# Driver.net
KiCad netlist of a schematic drawn in EAGLE
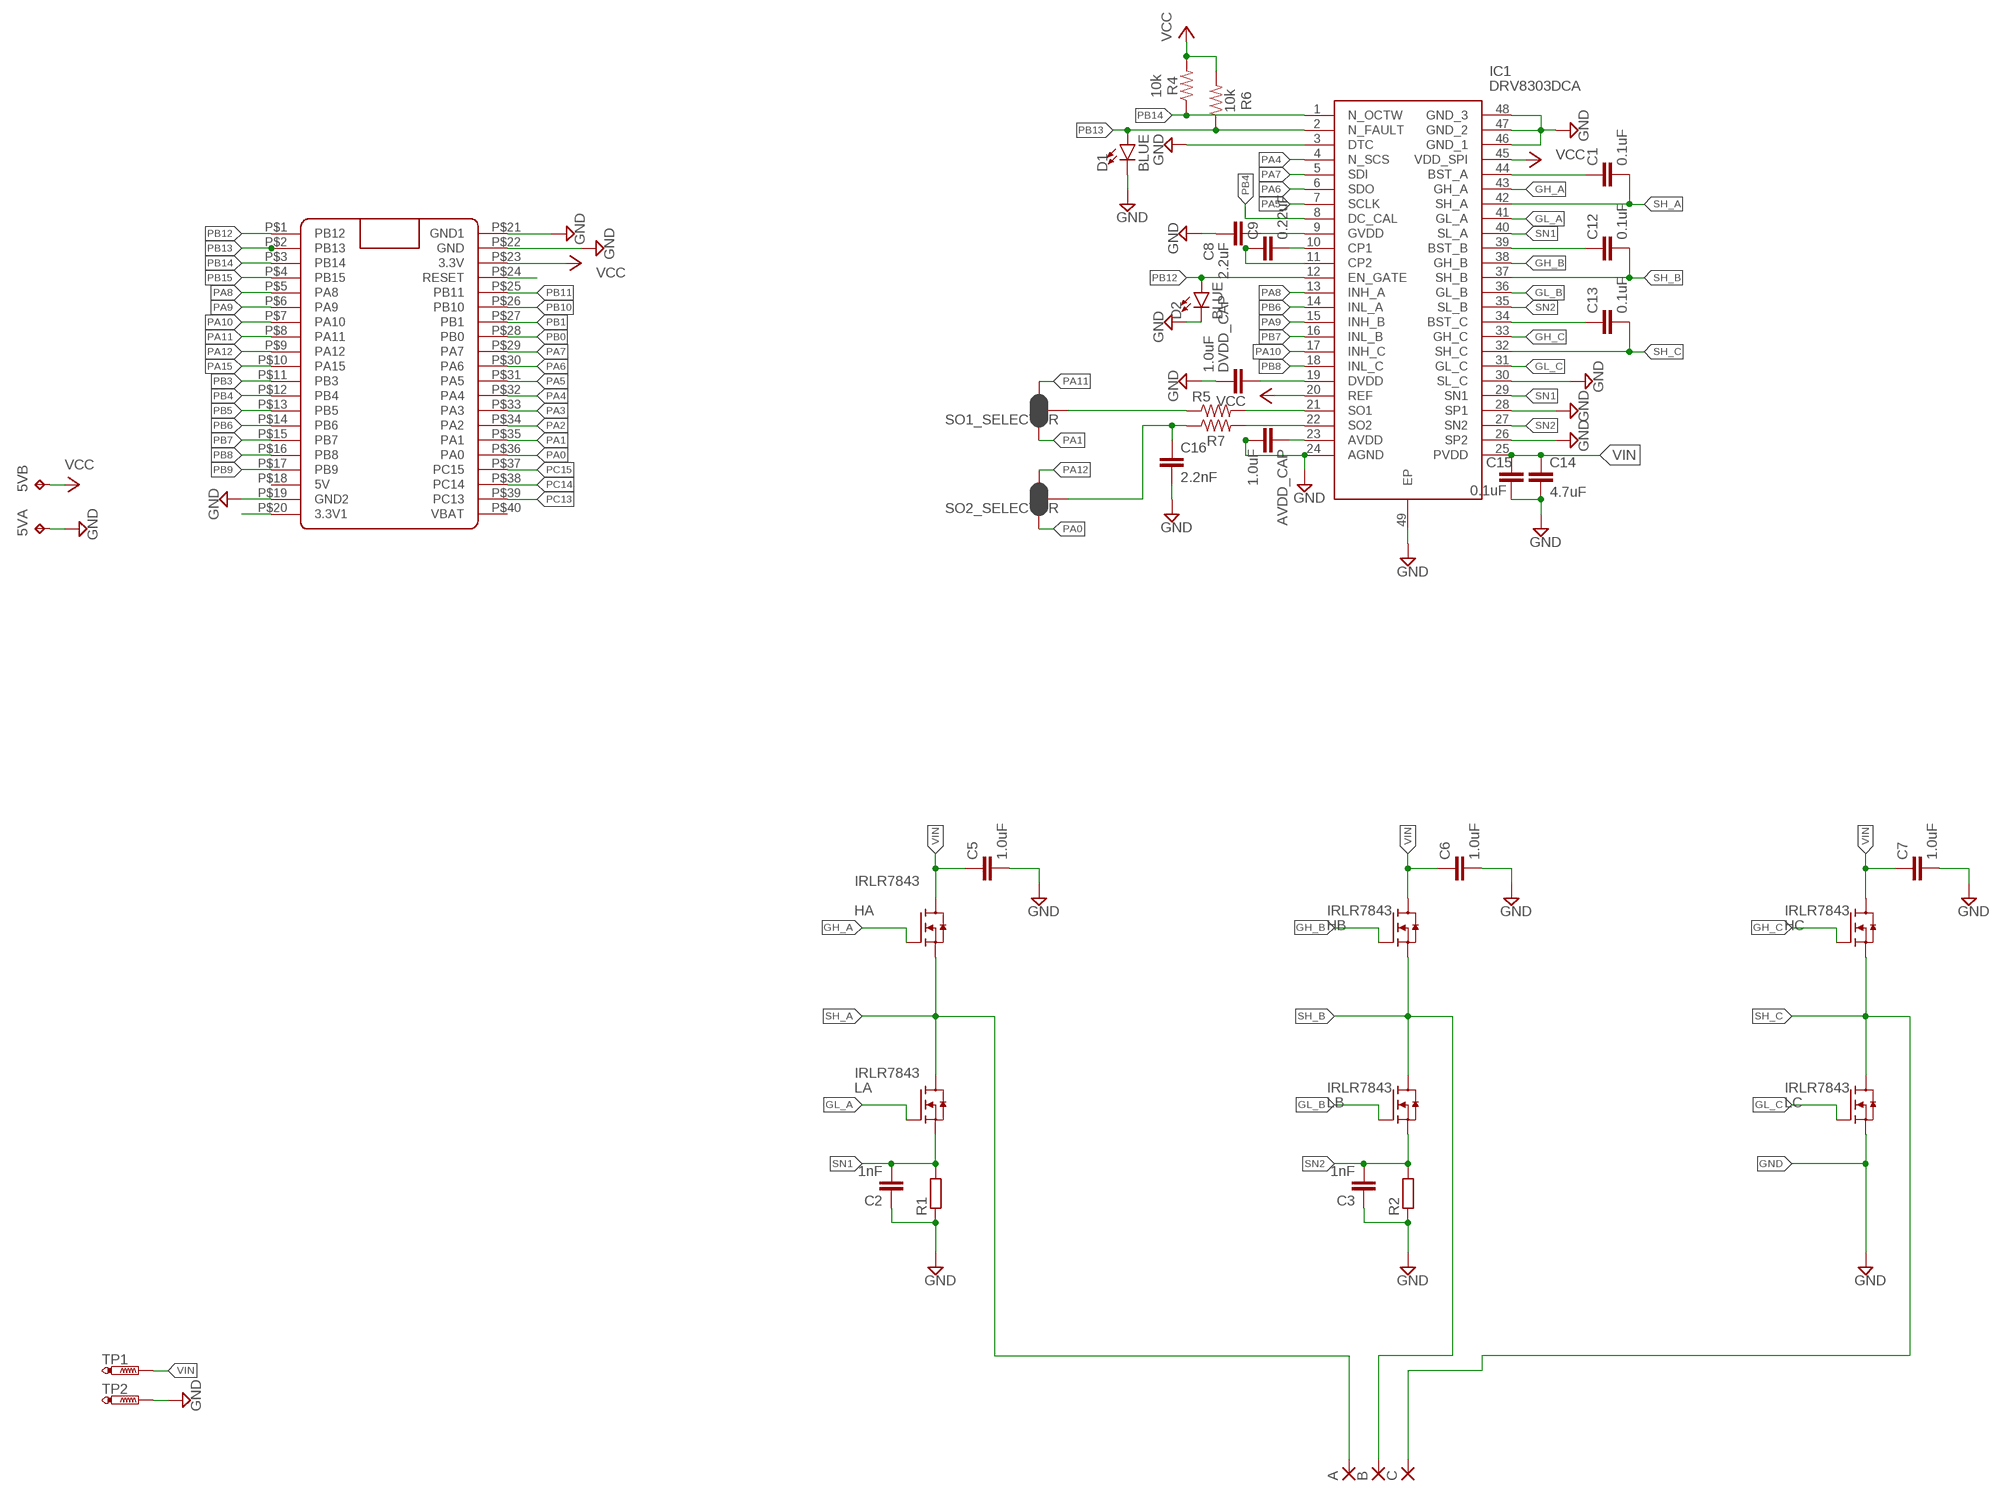
[diagram p0: schematic, sheet 1]

(export (version "E")
  (design (tool "Eeschema 10.0.6"))
  (components
    (comp (ref "5V")
      (value "TP2P2-38-17")
      (footprint "eagle-import:P2-38-17")
      (libsource (lib "eagle-import") (part "TP2P2-38-17"))
    )
    (comp (ref "A")
      (value "SMD5")
      (footprint "eagle-import:SMD2,54-5,08")
      (libsource (lib "eagle-import") (part "SMD5"))
    )
    (comp (ref "AVDD_CAP")
      (value "1.0uF")
      (footprint "eagle-import:0603")
      (libsource (lib "eagle-import") (part "1.0UF-0603-16V-10%"))
    )
    (comp (ref "B")
      (value "SMD5")
      (footprint "eagle-import:SMD2,54-5,08")
      (libsource (lib "eagle-import") (part "SMD5"))
    )
    (comp (ref "C")
      (value "SMD5")
      (footprint "eagle-import:SMD2,54-5,08")
      (libsource (lib "eagle-import") (part "SMD5"))
    )
    (comp (ref "C1")
      (value "0.1uF")
      (footprint "eagle-import:0603")
      (libsource (lib "eagle-import") (part "0.1UF-0603-25V-(+80/-20%)"))
    )
    (comp (ref "C2")
      (value "1nF")
      (footprint "eagle-import:0603")
      (libsource (lib "eagle-import") (part "1.0NF/1000PF-0603-50V-10%"))
    )
    (comp (ref "C3")
      (value "1nF")
      (footprint "eagle-import:0603")
      (libsource (lib "eagle-import") (part "1.0NF/1000PF-0603-50V-10%"))
    )
    (comp (ref "C5")
      (value "1.0uF")
      (footprint "eagle-import:0603")
      (libsource (lib "eagle-import") (part "1.0UF-0603-16V-10%-X7R"))
    )
    (comp (ref "C6")
      (value "1.0uF")
      (footprint "eagle-import:0603")
      (libsource (lib "eagle-import") (part "1.0UF-0603-16V-10%-X7R"))
    )
    (comp (ref "C7")
      (value "1.0uF")
      (footprint "eagle-import:0603")
      (libsource (lib "eagle-import") (part "1.0UF-0603-16V-10%-X7R"))
    )
    (comp (ref "C8")
      (value "2.2uF")
      (footprint "eagle-import:0603")
      (libsource (lib "eagle-import") (part "2.2UF-0603-10V-20%"))
    )
    (comp (ref "C9")
      (value "0.22uF")
      (footprint "eagle-import:0603")
      (libsource (lib "eagle-import") (part "0.22UF-0603-25V-10%"))
    )
    (comp (ref "C12")
      (value "0.1uF")
      (footprint "eagle-import:0603")
      (libsource (lib "eagle-import") (part "0.1UF-0603-25V-(+80/-20%)"))
    )
    (comp (ref "C13")
      (value "0.1uF")
      (footprint "eagle-import:0603")
      (libsource (lib "eagle-import") (part "0.1UF-0603-25V-(+80/-20%)"))
    )
    (comp (ref "C14")
      (value "4.7uF")
      (footprint "eagle-import:0603")
      (libsource (lib "eagle-import") (part "4.7UF-0603-35V-(20%)"))
    )
    (comp (ref "C15")
      (value "0.1uF")
      (footprint "eagle-import:0603")
      (libsource (lib "eagle-import") (part "0.1UF-0603-25V-(+80/-20%)"))
    )
    (comp (ref "C16")
      (value "2.2nF")
      (footprint "eagle-import:0603")
      (libsource (lib "eagle-import") (part "2.2NF/2200PF-0603-50V-10%"))
    )
    (comp (ref "D1")
      (value "BLUE")
      (footprint "eagle-import:LED-0603")
      (libsource (lib "eagle-import") (part "LED-BLUE0603"))
    )
    (comp (ref "D2")
      (value "BLUE")
      (footprint "eagle-import:LED-0603")
      (libsource (lib "eagle-import") (part "LED-BLUE0603"))
    )
    (comp (ref "DVDD_CAP")
      (value "1.0uF")
      (footprint "eagle-import:0603")
      (libsource (lib "eagle-import") (part "1.0UF-0603-16V-10%"))
    )
    (comp (ref "HA")
      (value "IRLR7843")
      (footprint "eagle-import:TO252")
      (libsource (lib "eagle-import") (part "IRLR7843"))
    )
    (comp (ref "HB")
      (value "IRLR7843")
      (footprint "eagle-import:TO252")
      (libsource (lib "eagle-import") (part "IRLR7843"))
    )
    (comp (ref "HC")
      (value "IRLR7843")
      (footprint "eagle-import:TO252")
      (libsource (lib "eagle-import") (part "IRLR7843"))
    )
    (comp (ref "IC1")
      (value "DRV8303DCA")
      (footprint "eagle-import:SOP50P810X120-49N")
      (fields (field (name "MOUSER_PART_NUMBER") "595-DRV8303DCA"))
      (libsource (lib "eagle-import") (part "DRV8303DCA"))
    )
    (comp (ref "LA")
      (value "IRLR7843")
      (footprint "eagle-import:TO252")
      (libsource (lib "eagle-import") (part "IRLR7843"))
    )
    (comp (ref "LB")
      (value "IRLR7843")
      (footprint "eagle-import:TO252")
      (libsource (lib "eagle-import") (part "IRLR7843"))
    )
    (comp (ref "LC")
      (value "IRLR7843")
      (footprint "eagle-import:TO252")
      (libsource (lib "eagle-import") (part "IRLR7843"))
    )
    (comp (ref "R1")
      (value "R-EU_R2512")
      (footprint "eagle-import:R2512")
      (libsource (lib "eagle-import") (part "R-EU_R2512"))
    )
    (comp (ref "R2")
      (value "R-EU_R2512")
      (footprint "eagle-import:R2512")
      (libsource (lib "eagle-import") (part "R-EU_R2512"))
    )
    (comp (ref "R4")
      (value "10k")
      (footprint "eagle-import:0603")
      (libsource (lib "eagle-import") (part "10KOHM-0603-1/10W-1%"))
    )
    (comp (ref "R5")
      (value "0")
      (footprint "eagle-import:0603")
      (libsource (lib "eagle-import") (part "0OHM-0603-1/10W"))
    )
    (comp (ref "R6")
      (value "10k")
      (footprint "eagle-import:0603")
      (libsource (lib "eagle-import") (part "10KOHM-0603-1/10W-1%"))
    )
    (comp (ref "R7")
      (value "0")
      (footprint "eagle-import:0603")
      (libsource (lib "eagle-import") (part "0OHM-0603-1/10W"))
    )
    (comp (ref "SO1_SELECTOR")
      (value "JUMPER-SMT_3_2-NC_PASTE_SILK")
      (footprint "eagle-import:SMT-JUMPER_3_2-NC_PASTE_SILK")
      (libsource (lib "eagle-import") (part "JUMPER-SMT_3_2-NC_PASTE_SILK"))
    )
    (comp (ref "SO2_SELECTOR")
      (value "JUMPER-SMT_3_2-NC_PASTE_SILK")
      (footprint "eagle-import:SMT-JUMPER_3_2-NC_PASTE_SILK")
      (libsource (lib "eagle-import") (part "JUMPER-SMT_3_2-NC_PASTE_SILK"))
    )
    (comp (ref "TP1")
      (value "PTR1PAD1-20Y")
      (footprint "eagle-import:P1-20Y")
      (libsource (lib "eagle-import") (part "PTR1PAD1-20Y"))
    )
    (comp (ref "TP2")
      (value "PTR1PAD1-20Y")
      (footprint "eagle-import:P1-20Y")
      (libsource (lib "eagle-import") (part "PTR1PAD1-20Y"))
    )
    (comp (ref "U$1")
      (value "BLUE_PILLADVANCED")
      (footprint "eagle-import:BLUE_PILL_ADV")
      (libsource (lib "eagle-import") (part "BLUE_PILLADVANCED"))
    )
  )
  (nets
    (net (code "1") (name "GH_A") (class "Default")
      (node (ref "HA") (pin "1") (pinfunction "G_1") (pintype "passive"))
      (node (ref "IC1") (pin "43") (pinfunction "GH_A_43") (pintype "output"))
    )
    (net (code "2") (name "GH_B") (class "Default")
      (node (ref "HB") (pin "1") (pinfunction "G_1") (pintype "passive"))
      (node (ref "IC1") (pin "38") (pinfunction "GH_B_38") (pintype "output"))
    )
    (net (code "3") (name "GH_C") (class "Default")
      (node (ref "HC") (pin "1") (pinfunction "G_1") (pintype "passive"))
      (node (ref "IC1") (pin "33") (pinfunction "GH_C_33") (pintype "output"))
    )
    (net (code "4") (name "GL_A") (class "Default")
      (node (ref "IC1") (pin "41") (pinfunction "GL_A_41") (pintype "output"))
      (node (ref "LA") (pin "1") (pinfunction "G_1") (pintype "passive"))
    )
    (net (code "5") (name "GL_B") (class "Default")
      (node (ref "IC1") (pin "36") (pinfunction "GL_B_36") (pintype "output"))
      (node (ref "LB") (pin "1") (pinfunction "G_1") (pintype "passive"))
    )
    (net (code "6") (name "GL_C") (class "Default")
      (node (ref "IC1") (pin "31") (pinfunction "GL_C_31") (pintype "output"))
      (node (ref "LC") (pin "1") (pinfunction "G_1") (pintype "passive"))
    )
    (net (code "7") (name "GND") (class "Default")
      (node (ref "5V") (pin "TP-1") (pinfunction "TP_TP-1") (pintype "input"))
      (node (ref "AVDD_CAP") (pin "2") (pinfunction "2_2") (pintype "passive"))
      (node (ref "C14") (pin "2") (pinfunction "2_2") (pintype "passive"))
      (node (ref "C15") (pin "2") (pinfunction "2_2") (pintype "passive"))
      (node (ref "C16") (pin "2") (pinfunction "2_2") (pintype "passive"))
      (node (ref "C2") (pin "1") (pinfunction "1_1") (pintype "passive"))
      (node (ref "C3") (pin "1") (pinfunction "1_1") (pintype "passive"))
      (node (ref "C5") (pin "2") (pinfunction "2_2") (pintype "passive"))
      (node (ref "C6") (pin "2") (pinfunction "2_2") (pintype "passive"))
      (node (ref "C7") (pin "2") (pinfunction "2_2") (pintype "passive"))
      (node (ref "C8") (pin "2") (pinfunction "2_2") (pintype "passive"))
      (node (ref "D1") (pin "C") (pinfunction "C_C") (pintype "passive"))
      (node (ref "D2") (pin "C") (pinfunction "C_C") (pintype "passive"))
      (node (ref "DVDD_CAP") (pin "1") (pinfunction "1_1") (pintype "passive"))
      (node (ref "IC1") (pin "24") (pinfunction "AGND_24") (pintype "power_in"))
      (node (ref "IC1") (pin "26") (pinfunction "SP2_26") (pintype "input"))
      (node (ref "IC1") (pin "28") (pinfunction "SP1_28") (pintype "input"))
      (node (ref "IC1") (pin "3") (pinfunction "DTC_3") (pintype "input"))
      (node (ref "IC1") (pin "30") (pinfunction "SL_C_30") (pintype "input"))
      (node (ref "IC1") (pin "46") (pinfunction "GND_1_46") (pintype "power_in"))
      (node (ref "IC1") (pin "47") (pinfunction "GND_2_47") (pintype "power_in"))
      (node (ref "IC1") (pin "48") (pinfunction "GND_3_48") (pintype "power_in"))
      (node (ref "IC1") (pin "49") (pinfunction "EP_49") (pintype "bidirectional"))
      (node (ref "LC") (pin "2") (pinfunction "S_2") (pintype "passive"))
      (node (ref "R1") (pin "1") (pinfunction "1_1") (pintype "passive"))
      (node (ref "R2") (pin "1") (pinfunction "1_1") (pintype "passive"))
      (node (ref "TP2") (pin "TP") (pinfunction "TP_TP") (pintype "input"))
      (node (ref "U$1") (pin "P$19") (pinfunction "GND2_P$19") (pintype "bidirectional"))
      (node (ref "U$1") (pin "P$21") (pinfunction "GND1_P$21") (pintype "power_in"))
      (node (ref "U$1") (pin "P$22") (pinfunction "GND_P$22") (pintype "bidirectional"))
    )
    (net (code "8") (name "Net-(C16-Pad1)") (class "Default")
      (node (ref "C16") (pin "1") (pinfunction "1_1") (pintype "passive"))
      (node (ref "R7") (pin "1") (pinfunction "1_1") (pintype "passive"))
      (node (ref "SO2_SELECTOR") (pin "2") (pinfunction "2_2") (pintype "passive"))
    )
    (net (code "9") (name "Net-(IC1-AVDD)") (class "Default")
      (node (ref "AVDD_CAP") (pin "1") (pinfunction "1_1") (pintype "passive"))
      (node (ref "IC1") (pin "23") (pinfunction "AVDD_23") (pintype "power_in"))
    )
    (net (code "10") (name "Net-(IC1-BST_A)") (class "Default")
      (node (ref "C1") (pin "1") (pinfunction "1_1") (pintype "passive"))
      (node (ref "IC1") (pin "44") (pinfunction "BST_A_44") (pintype "bidirectional"))
    )
    (net (code "11") (name "Net-(IC1-BST_B)") (class "Default")
      (node (ref "C12") (pin "1") (pinfunction "1_1") (pintype "passive"))
      (node (ref "IC1") (pin "39") (pinfunction "BST_B_39") (pintype "bidirectional"))
    )
    (net (code "12") (name "Net-(IC1-BST_C)") (class "Default")
      (node (ref "C13") (pin "1") (pinfunction "1_1") (pintype "passive"))
      (node (ref "IC1") (pin "34") (pinfunction "BST_C_34") (pintype "bidirectional"))
    )
    (net (code "13") (name "Net-(IC1-CP1)") (class "Default")
      (node (ref "C9") (pin "2") (pinfunction "2_2") (pintype "passive"))
      (node (ref "IC1") (pin "10") (pinfunction "CP1_10") (pintype "power_in"))
    )
    (net (code "14") (name "Net-(IC1-CP2)") (class "Default")
      (node (ref "C9") (pin "1") (pinfunction "1_1") (pintype "passive"))
      (node (ref "IC1") (pin "11") (pinfunction "CP2_11") (pintype "power_in"))
    )
    (net (code "15") (name "Net-(IC1-DVDD)") (class "Default")
      (node (ref "DVDD_CAP") (pin "2") (pinfunction "2_2") (pintype "passive"))
      (node (ref "IC1") (pin "19") (pinfunction "DVDD_19") (pintype "power_in"))
    )
    (net (code "16") (name "Net-(IC1-GVDD)") (class "Default")
      (node (ref "C8") (pin "1") (pinfunction "1_1") (pintype "passive"))
      (node (ref "IC1") (pin "9") (pinfunction "GVDD_9") (pintype "power_in"))
    )
    (net (code "17") (name "Net-(IC1-SO1)") (class "Default")
      (node (ref "IC1") (pin "21") (pinfunction "SO1_21") (pintype "output"))
      (node (ref "R5") (pin "2") (pinfunction "2_2") (pintype "passive"))
    )
    (net (code "18") (name "Net-(IC1-SO2)") (class "Default")
      (node (ref "IC1") (pin "22") (pinfunction "SO2_22") (pintype "output"))
      (node (ref "R7") (pin "2") (pinfunction "2_2") (pintype "passive"))
    )
    (net (code "19") (name "Net-(R5-Pad1)") (class "Default")
      (node (ref "R5") (pin "1") (pinfunction "1_1") (pintype "passive"))
      (node (ref "SO1_SELECTOR") (pin "2") (pinfunction "2_2") (pintype "passive"))
    )
    (net (code "20") (name "PA0") (class "Default")
      (node (ref "SO2_SELECTOR") (pin "1") (pinfunction "1_1") (pintype "passive"))
      (node (ref "U$1") (pin "P$36") (pinfunction "PA0_P$36") (pintype "bidirectional"))
    )
    (net (code "21") (name "PA1") (class "Default")
      (node (ref "SO1_SELECTOR") (pin "1") (pinfunction "1_1") (pintype "passive"))
      (node (ref "U$1") (pin "P$35") (pinfunction "PA1_P$35") (pintype "bidirectional"))
    )
    (net (code "22") (name "PA2") (class "Default")
      (node (ref "U$1") (pin "P$34") (pinfunction "PA2_P$34") (pintype "bidirectional"))
    )
    (net (code "23") (name "PA3") (class "Default")
      (node (ref "U$1") (pin "P$33") (pinfunction "PA3_P$33") (pintype "bidirectional"))
    )
    (net (code "24") (name "PA4") (class "Default")
      (node (ref "IC1") (pin "4") (pinfunction "N_SCS_4") (pintype "input"))
      (node (ref "U$1") (pin "P$32") (pinfunction "PA4_P$32") (pintype "bidirectional"))
    )
    (net (code "25") (name "PA5") (class "Default")
      (node (ref "IC1") (pin "7") (pinfunction "SCLK_7") (pintype "input"))
      (node (ref "U$1") (pin "P$31") (pinfunction "PA5_P$31") (pintype "bidirectional"))
    )
    (net (code "26") (name "PA6") (class "Default")
      (node (ref "IC1") (pin "6") (pinfunction "SDO_6") (pintype "output"))
      (node (ref "U$1") (pin "P$30") (pinfunction "PA6_P$30") (pintype "bidirectional"))
    )
    (net (code "27") (name "PA7") (class "Default")
      (node (ref "IC1") (pin "5") (pinfunction "SDI_5") (pintype "input"))
      (node (ref "U$1") (pin "P$29") (pinfunction "PA7_P$29") (pintype "bidirectional"))
    )
    (net (code "28") (name "PA8") (class "Default")
      (node (ref "IC1") (pin "13") (pinfunction "INH_A_13") (pintype "input"))
      (node (ref "U$1") (pin "P$5") (pinfunction "PA8_P$5") (pintype "bidirectional"))
    )
    (net (code "29") (name "PA9") (class "Default")
      (node (ref "IC1") (pin "15") (pinfunction "INH_B_15") (pintype "input"))
      (node (ref "U$1") (pin "P$6") (pinfunction "PA9_P$6") (pintype "bidirectional"))
    )
    (net (code "30") (name "PA10") (class "Default")
      (node (ref "IC1") (pin "17") (pinfunction "INH_C_17") (pintype "input"))
      (node (ref "U$1") (pin "P$7") (pinfunction "PA10_P$7") (pintype "bidirectional"))
    )
    (net (code "31") (name "PA11") (class "Default")
      (node (ref "SO1_SELECTOR") (pin "3") (pinfunction "3_3") (pintype "passive"))
      (node (ref "U$1") (pin "P$8") (pinfunction "PA11_P$8") (pintype "bidirectional"))
    )
    (net (code "32") (name "PA12") (class "Default")
      (node (ref "SO2_SELECTOR") (pin "3") (pinfunction "3_3") (pintype "passive"))
      (node (ref "U$1") (pin "P$9") (pinfunction "PA12_P$9") (pintype "bidirectional"))
    )
    (net (code "33") (name "PA15") (class "Default")
      (node (ref "U$1") (pin "P$10") (pinfunction "PA15_P$10") (pintype "bidirectional"))
    )
    (net (code "34") (name "PB0") (class "Default")
      (node (ref "U$1") (pin "P$28") (pinfunction "PB0_P$28") (pintype "bidirectional"))
    )
    (net (code "35") (name "PB1") (class "Default")
      (node (ref "U$1") (pin "P$27") (pinfunction "PB1_P$27") (pintype "bidirectional"))
    )
    (net (code "36") (name "PB3") (class "Default")
      (node (ref "U$1") (pin "P$11") (pinfunction "PB3_P$11") (pintype "bidirectional"))
    )
    (net (code "37") (name "PB4") (class "Default")
      (node (ref "IC1") (pin "8") (pinfunction "DC_CAL_8") (pintype "input"))
      (node (ref "U$1") (pin "P$12") (pinfunction "PB4_P$12") (pintype "bidirectional"))
    )
    (net (code "38") (name "PB5") (class "Default")
      (node (ref "U$1") (pin "P$13") (pinfunction "PB5_P$13") (pintype "bidirectional"))
    )
    (net (code "39") (name "PB6") (class "Default")
      (node (ref "IC1") (pin "14") (pinfunction "INL_A_14") (pintype "input"))
      (node (ref "U$1") (pin "P$14") (pinfunction "PB6_P$14") (pintype "bidirectional"))
    )
    (net (code "40") (name "PB7") (class "Default")
      (node (ref "IC1") (pin "16") (pinfunction "INL_B_16") (pintype "input"))
      (node (ref "U$1") (pin "P$15") (pinfunction "PB7_P$15") (pintype "bidirectional"))
    )
    (net (code "41") (name "PB8") (class "Default")
      (node (ref "IC1") (pin "18") (pinfunction "INL_C_18") (pintype "input"))
      (node (ref "U$1") (pin "P$16") (pinfunction "PB8_P$16") (pintype "bidirectional"))
    )
    (net (code "42") (name "PB9") (class "Default")
      (node (ref "U$1") (pin "P$17") (pinfunction "PB9_P$17") (pintype "bidirectional"))
    )
    (net (code "43") (name "PB10") (class "Default")
      (node (ref "U$1") (pin "P$26") (pinfunction "PB10_P$26") (pintype "bidirectional"))
    )
    (net (code "44") (name "PB11") (class "Default")
      (node (ref "U$1") (pin "P$25") (pinfunction "PB11_P$25") (pintype "bidirectional"))
    )
    (net (code "45") (name "PB12") (class "Default")
      (node (ref "D2") (pin "A") (pinfunction "A_A") (pintype "passive"))
      (node (ref "IC1") (pin "12") (pinfunction "EN_GATE_12") (pintype "input"))
      (node (ref "U$1") (pin "P$1") (pinfunction "PB12_P$1") (pintype "bidirectional"))
    )
    (net (code "46") (name "PB13") (class "Default")
      (node (ref "D1") (pin "A") (pinfunction "A_A") (pintype "passive"))
      (node (ref "IC1") (pin "2") (pinfunction "N_FAULT_2") (pintype "output"))
      (node (ref "R6") (pin "1") (pinfunction "1_1") (pintype "passive"))
      (node (ref "U$1") (pin "P$2") (pinfunction "PB13_P$2") (pintype "bidirectional"))
    )
    (net (code "47") (name "PB14") (class "Default")
      (node (ref "IC1") (pin "1") (pinfunction "N_OCTW_1") (pintype "output"))
      (node (ref "R4") (pin "1") (pinfunction "1_1") (pintype "passive"))
      (node (ref "U$1") (pin "P$3") (pinfunction "PB14_P$3") (pintype "bidirectional"))
    )
    (net (code "48") (name "PB15") (class "Default")
      (node (ref "U$1") (pin "P$4") (pinfunction "PB15_P$4") (pintype "bidirectional"))
    )
    (net (code "49") (name "PC13") (class "Default")
      (node (ref "U$1") (pin "P$39") (pinfunction "PC13_P$39") (pintype "bidirectional"))
    )
    (net (code "50") (name "PC14") (class "Default")
      (node (ref "U$1") (pin "P$38") (pinfunction "PC14_P$38") (pintype "bidirectional"))
    )
    (net (code "51") (name "PC15") (class "Default")
      (node (ref "U$1") (pin "P$37") (pinfunction "PC15_P$37") (pintype "bidirectional"))
    )
    (net (code "52") (name "SH_A") (class "Default")
      (node (ref "A") (pin "1") (pinfunction "P_1") (pintype "passive"))
      (node (ref "C1") (pin "2") (pinfunction "2_2") (pintype "passive"))
      (node (ref "HA") (pin "2") (pinfunction "S_2") (pintype "passive"))
      (node (ref "IC1") (pin "42") (pinfunction "SH_A_42") (pintype "input"))
      (node (ref "LA") (pin "3") (pinfunction "D_3") (pintype "passive"))
    )
    (net (code "53") (name "SH_B") (class "Default")
      (node (ref "B") (pin "1") (pinfunction "P_1") (pintype "passive"))
      (node (ref "C12") (pin "2") (pinfunction "2_2") (pintype "passive"))
      (node (ref "HB") (pin "2") (pinfunction "S_2") (pintype "passive"))
      (node (ref "IC1") (pin "37") (pinfunction "SH_B_37") (pintype "input"))
      (node (ref "LB") (pin "3") (pinfunction "D_3") (pintype "passive"))
    )
    (net (code "54") (name "SH_C") (class "Default")
      (node (ref "C") (pin "1") (pinfunction "P_1") (pintype "passive"))
      (node (ref "C13") (pin "2") (pinfunction "2_2") (pintype "passive"))
      (node (ref "HC") (pin "2") (pinfunction "S_2") (pintype "passive"))
      (node (ref "IC1") (pin "32") (pinfunction "SH_C_32") (pintype "input"))
      (node (ref "LC") (pin "3") (pinfunction "D_3") (pintype "passive"))
    )
    (net (code "55") (name "SN1") (class "Default")
      (node (ref "C2") (pin "2") (pinfunction "2_2") (pintype "passive"))
      (node (ref "IC1") (pin "29") (pinfunction "SN1_29") (pintype "input"))
      (node (ref "IC1") (pin "40") (pinfunction "SL_A_40") (pintype "input"))
      (node (ref "LA") (pin "2") (pinfunction "S_2") (pintype "passive"))
      (node (ref "R1") (pin "2") (pinfunction "2_2") (pintype "passive"))
    )
    (net (code "56") (name "SN2") (class "Default")
      (node (ref "C3") (pin "2") (pinfunction "2_2") (pintype "passive"))
      (node (ref "IC1") (pin "27") (pinfunction "SN2_27") (pintype "input"))
      (node (ref "IC1") (pin "35") (pinfunction "SL_B_35") (pintype "input"))
      (node (ref "LB") (pin "2") (pinfunction "S_2") (pintype "passive"))
      (node (ref "R2") (pin "2") (pinfunction "2_2") (pintype "passive"))
    )
    (net (code "57") (name "VCC") (class "Default")
      (node (ref "5V") (pin "TP-2") (pinfunction "TP_TP-2") (pintype "input"))
      (node (ref "IC1") (pin "20") (pinfunction "REF_20") (pintype "input"))
      (node (ref "IC1") (pin "45") (pinfunction "VDD_SPI_45") (pintype "power_in"))
      (node (ref "R4") (pin "2") (pinfunction "2_2") (pintype "passive"))
      (node (ref "R6") (pin "2") (pinfunction "2_2") (pintype "passive"))
      (node (ref "U$1") (pin "P$23") (pinfunction "3.3V_P$23") (pintype "bidirectional"))
    )
    (net (code "58") (name "VIN") (class "Default")
      (node (ref "C14") (pin "1") (pinfunction "1_1") (pintype "passive"))
      (node (ref "C15") (pin "1") (pinfunction "1_1") (pintype "passive"))
      (node (ref "C5") (pin "1") (pinfunction "1_1") (pintype "passive"))
      (node (ref "C6") (pin "1") (pinfunction "1_1") (pintype "passive"))
      (node (ref "C7") (pin "1") (pinfunction "1_1") (pintype "passive"))
      (node (ref "HA") (pin "3") (pinfunction "D_3") (pintype "passive"))
      (node (ref "HB") (pin "3") (pinfunction "D_3") (pintype "passive"))
      (node (ref "HC") (pin "3") (pinfunction "D_3") (pintype "passive"))
      (node (ref "IC1") (pin "25") (pinfunction "PVDD_25") (pintype "power_in"))
      (node (ref "TP1") (pin "TP") (pinfunction "TP_TP") (pintype "input"))
    )
    (net (code "59") (name "unconnected-(U$1-3.3V1-PadP$20)") (class "Default")
      (node (ref "U$1") (pin "P$20") (pinfunction "3.3V1_P$20") (pintype "bidirectional"))
    )
    (net (code "60") (name "unconnected-(U$1-5V-PadP$18)") (class "Default")
      (node (ref "U$1") (pin "P$18") (pinfunction "5V_P$18") (pintype "bidirectional"))
    )
    (net (code "61") (name "unconnected-(U$1-RESET-PadP$24)") (class "Default")
      (node (ref "U$1") (pin "P$24") (pinfunction "RESET_P$24") (pintype "bidirectional"))
    )
    (net (code "62") (name "unconnected-(U$1-VBAT-PadP$40)") (class "Default")
      (node (ref "U$1") (pin "P$40") (pinfunction "VBAT_P$40") (pintype "bidirectional"))
    )
  )
)
